# SCH_SA45_DaughterCard.net
KiCad netlist of a schematic drawn in Altium Designer
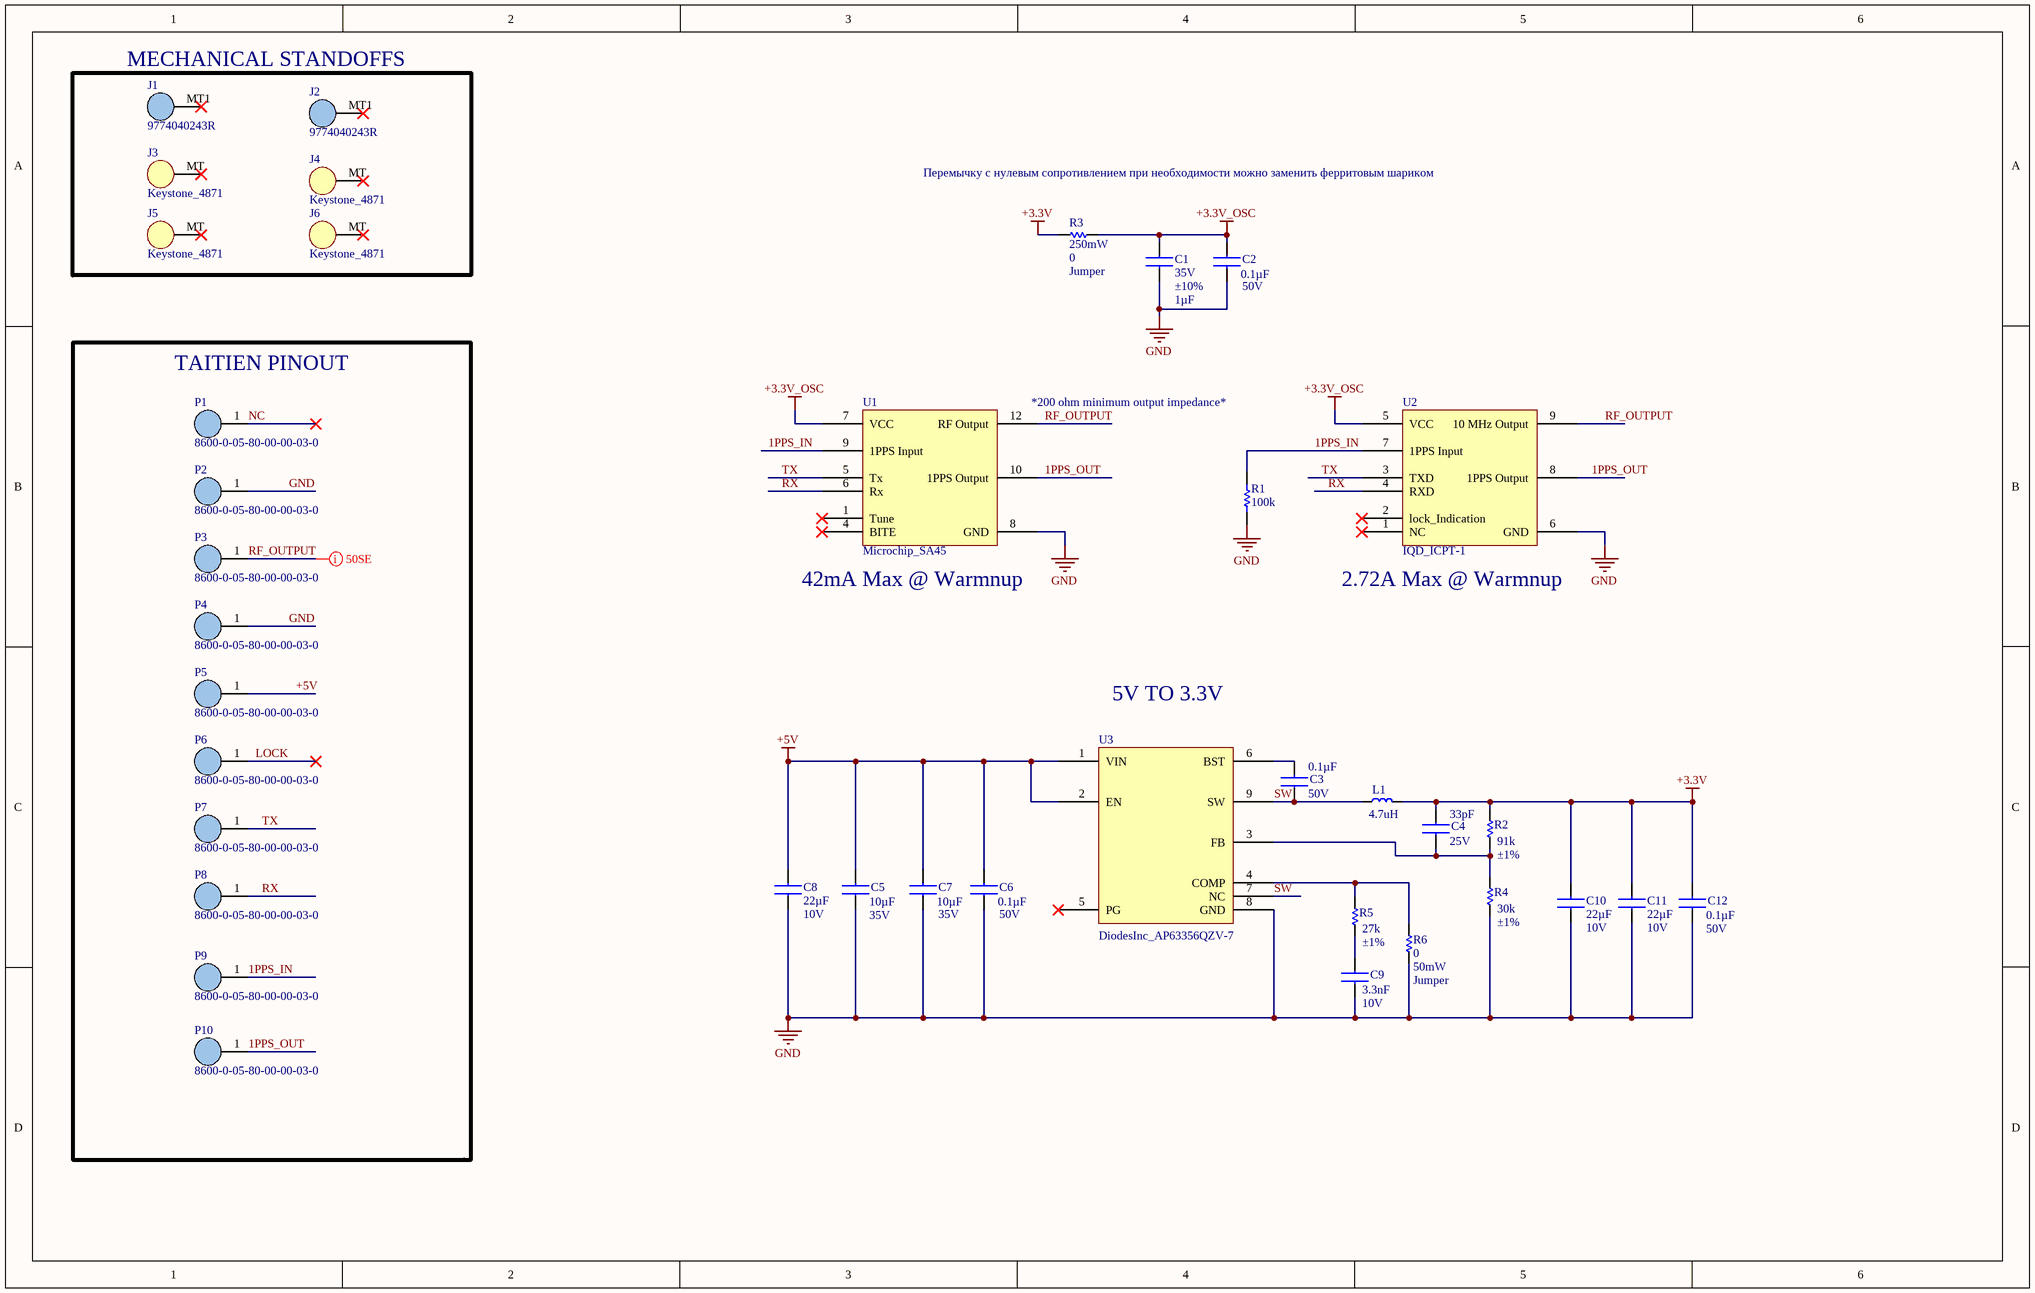
[diagram p0: SCH_SA45_DaughterCard.SchDoc]

(export (version "E")
  (design (tool "Eeschema 10.0.6"))
  (components
    (comp (ref "C1")
      (value "Murata_GRM155R6YA105KE11D")
      (footprint "CAPC1005X061N")
      (description "CAP, CER, X5R, 1UF, 10%, 35V, 0402, 0.55MM T")
      (fields
        (field (name "VOLTAGE RATING") "35V")
        (field (name "TOLERANCE") "±10%")
        (field (name "CAPACITANCE") "1µF")
        (field (name "MANUFACTURER PART NUMBER") "GRM155R6YA105KE11D")
        (field (name "MANUFACTURER") "Murata")
      )
      (libsource (lib "RL Research Altium Server") (part "Capacitor_300mil"))
    )
    (comp (ref "C2")
      (value "Murata_GRM155R61H104KE14D")
      (footprint "CAPC1005X055N")
      (description "CAP, CER, X5R, 0.10UF, 10%, 50V, 0402, 0.55MM T")
      (fields
        (field (name "TOLERANCE") "±10%")
        (field (name "VOLTAGE RATING") "50V")
        (field (name "MANUFACTURER PART NUMBER") "GRM155R61H104KE14D")
        (field (name "CAPACITANCE") "0.1µF")
      )
      (libsource (lib "RL Research Altium Server") (part "Capacitor_300mil"))
    )
    (comp (ref "C3")
      (value "Murata_GRM155R61H104KE14D")
      (footprint "CAPC1005X055N")
      (description "CAP, CER, X5R, 0.10UF, 10%, 50V, 0402, 0.55MM T")
      (fields
        (field (name "TOLERANCE") "±10%")
        (field (name "VOLTAGE RATING") "50V")
        (field (name "MANUFACTURER PART NUMBER") "GRM155R61H104KE14D")
        (field (name "CAPACITANCE") "0.1µF")
      )
      (libsource (lib "RL Research Altium Server") (part "Capacitor_300mil"))
    )
    (comp (ref "C4")
      (value "Murata_GRM0335C1E330JA01D")
      (footprint "CAPC0603X033N")
      (description "CAP, CER, NP0, 33PF, 5%, 25V, 0201, 0.33MM T")
      (fields
        (field (name "MANUFACTURER") "Murata")
        (field (name "CAPACITANCE") "33pF")
        (field (name "TOLERANCE") "±5%")
        (field (name "VOLTAGE RATING") "25V")
      )
      (libsource (lib "RL Research Altium Server") (part "Capacitor_300mil"))
    )
    (comp (ref "C5")
      (value "Murata_GRM21BR6YA106KE43L")
      (footprint "CAPC2013X145N")
      (description "CAP, CER, X5R, 10UF, 10%, 35V, 0805, 1.45MM T")
      (fields
        (field (name "MANUFACTURER") "Murata")
        (field (name "MANUFACTURER PART NUMBER") "GRM21BR6YA106KE43L")
        (field (name "VOLTAGE RATING") "35V")
        (field (name "CAPACITANCE") "10µF")
      )
      (libsource (lib "RL Research Altium Server") (part "Capacitor_300mil"))
    )
    (comp (ref "C6")
      (value "Murata_GRM155R61H104KE14D")
      (footprint "CAPC1005X055N")
      (description "CAP, CER, X5R, 0.10UF, 10%, 50V, 0402, 0.55MM T")
      (fields
        (field (name "TOLERANCE") "±10%")
        (field (name "VOLTAGE RATING") "50V")
        (field (name "MANUFACTURER PART NUMBER") "GRM155R61H104KE14D")
        (field (name "CAPACITANCE") "0.1µF")
      )
      (libsource (lib "RL Research Altium Server") (part "Capacitor_300mil"))
    )
    (comp (ref "C7")
      (value "Murata_GRM21BR6YA106KE43L")
      (footprint "CAPC2013X145N")
      (description "CAP, CER, X5R, 10UF, 10%, 35V, 0805, 1.45MM T")
      (fields
        (field (name "MANUFACTURER") "Murata")
        (field (name "MANUFACTURER PART NUMBER") "GRM21BR6YA106KE43L")
        (field (name "VOLTAGE RATING") "35V")
        (field (name "CAPACITANCE") "10µF")
      )
      (libsource (lib "RL Research Altium Server") (part "Capacitor_300mil"))
    )
    (comp (ref "C8")
      (value "Murata_GRM21BR61A226ME51L")
      (footprint "CAPC2013X140N")
      (description "CAP, CER, X5R, 22UF, 20%, 10V, 0805, 1.40MM T")
      (fields
        (field (name "CAPACITANCE") "22µF")
        (field (name "VOLTAGE RATING") "10V")
        (field (name "MANUFACTURER PART NUMBER") "GRM21BR61A226ME51L")
        (field (name "TOLERANCE") "±20%")
      )
      (libsource (lib "FRL Altium Server") (part "Capacitor_300mil"))
    )
    (comp (ref "C9")
      (value "Murata_GRM033R61A332KA01D")
      (footprint "CAPC0603X033N")
      (description "CAP, CER, X5R, 3300PF, 10%, 10V, 0201, 0.33MM T")
      (fields
        (field (name "TOLERANCE") "±10%")
        (field (name "MANUFACTURER PART NUMBER") "GRM033R61A332KA01D")
        (field (name "CAPACITANCE") "3.3nF")
        (field (name "VOLTAGE RATING") "10V")
      )
      (libsource (lib "RL Research Altium Server") (part "Capacitor_300mil"))
    )
    (comp (ref "C10")
      (value "Murata_GRM21BR61A226ME51L")
      (footprint "CAPC2013X140N")
      (description "CAP, CER, X5R, 22UF, 20%, 10V, 0805, 1.40MM T")
      (fields
        (field (name "CAPACITANCE") "22µF")
        (field (name "VOLTAGE RATING") "10V")
        (field (name "MANUFACTURER PART NUMBER") "GRM21BR61A226ME51L")
        (field (name "TOLERANCE") "±20%")
      )
      (libsource (lib "FRL Altium Server") (part "Capacitor_300mil"))
    )
    (comp (ref "C11")
      (value "Murata_GRM21BR61A226ME51L")
      (footprint "CAPC2013X140N")
      (description "CAP, CER, X5R, 22UF, 20%, 10V, 0805, 1.40MM T")
      (fields
        (field (name "CAPACITANCE") "22µF")
        (field (name "VOLTAGE RATING") "10V")
        (field (name "MANUFACTURER PART NUMBER") "GRM21BR61A226ME51L")
        (field (name "TOLERANCE") "±20%")
      )
      (libsource (lib "FRL Altium Server") (part "Capacitor_300mil"))
    )
    (comp (ref "C12")
      (value "Murata_GRM155R61H104KE14D")
      (footprint "CAPC1005X055N")
      (description "CAP, CER, X5R, 0.10UF, 10%, 50V, 0402, 0.55MM T")
      (fields
        (field (name "TOLERANCE") "±10%")
        (field (name "VOLTAGE RATING") "50V")
        (field (name "MANUFACTURER PART NUMBER") "GRM155R61H104KE14D")
        (field (name "CAPACITANCE") "0.1µF")
      )
      (libsource (lib "RL Research Altium Server") (part "Capacitor_300mil"))
    )
    (comp (ref "J1")
      (value "Wurth_9774040243R")
      (footprint "TH000V_300DIAx400_001mt_9774040243R")
      (description "STANDOFF, ROUND, M2X0.4 STEEL 4MM, 9774040243R")
      (fields
        (field (name "MANUFACTURER PART NUMBER") "9774040243R")
        (field (name "MANUFACTURER") "Wurth Elektronik")
      )
      (libsource (lib "FRL Altium Server") (part "CONN_SR_000pin_001mt_RND_F"))
    )
    (comp (ref "J2")
      (value "Wurth_9774040243R")
      (footprint "TH000V_300DIAx400_001mt_9774040243R")
      (description "STANDOFF, ROUND, M2X0.4 STEEL 4MM, 9774040243R")
      (fields
        (field (name "MANUFACTURER PART NUMBER") "9774040243R")
        (field (name "MANUFACTURER") "Wurth Elektronik")
      )
      (libsource (lib "FRL Altium Server") (part "CONN_SR_000pin_001mt_RND_F"))
    )
    (comp (ref "J3")
      (value "Keystone_4871")
      (footprint "Keystone_4871")
      (fields
        (field (name "MANUFACTURER") "Keystone Electronics")
        (field (name "MANUFACTURER PART NUMBER") "4871")
      )
      (libsource (lib "SCH_SA45_DaughterCard") (part "Keystone_4871"))
    )
    (comp (ref "J4")
      (value "Keystone_4871")
      (footprint "Keystone_4871")
      (fields
        (field (name "MANUFACTURER") "Keystone Electronics")
        (field (name "MANUFACTURER PART NUMBER") "4871")
      )
      (libsource (lib "SCH_SA45_DaughterCard") (part "Keystone_4871"))
    )
    (comp (ref "J5")
      (value "Keystone_4871")
      (footprint "Keystone_4871")
      (fields
        (field (name "MANUFACTURER") "Keystone Electronics")
        (field (name "MANUFACTURER PART NUMBER") "4871")
      )
      (libsource (lib "SCH_SA45_DaughterCard") (part "Keystone_4871"))
    )
    (comp (ref "J6")
      (value "Keystone_4871")
      (footprint "Keystone_4871")
      (fields
        (field (name "MANUFACTURER") "Keystone Electronics")
        (field (name "MANUFACTURER PART NUMBER") "4871")
      )
      (libsource (lib "SCH_SA45_DaughterCard") (part "Keystone_4871"))
    )
    (comp (ref "L1")
      (value "4.7uH")
      (footprint "Eaton_HCM0703-4R7-R")
      (fields (field (name "MANUFACTURER") "Eaton") (field (name "MANUFACTURER PART NUMBER") "HCM0703-4R7-R"))
      (libsource (lib "SCH_SA45_DaughterCard") (part "Inductor_Eaton"))
    )
    (comp (ref "P1")
      (value "Mill-Max_8600-0-05-80-00-00-03-0")
      (footprint "TH001V_109DIA_000mt_8600-0")
      (description "CONN, PC PIN, PRESS-FIT, 10.16MM LENGTH, TIN, TH")
      (fields
        (field (name "MANUFACTURER PART NUMBER") "8600-0-05-80-00-00-03-0")
        (field (name "MANUFACTURER") "Mill-Max Manufacturing Corp.")
      )
      (libsource (lib "FRL Altium Server") (part "CONN_SR_001pin_000mt_RND_M"))
    )
    (comp (ref "P2")
      (value "Mill-Max_8600-0-05-80-00-00-03-0")
      (footprint "TH001V_109DIA_000mt_8600-0")
      (description "CONN, PC PIN, PRESS-FIT, 10.16MM LENGTH, TIN, TH")
      (fields
        (field (name "MANUFACTURER PART NUMBER") "8600-0-05-80-00-00-03-0")
        (field (name "MANUFACTURER") "Mill-Max Manufacturing Corp.")
      )
      (libsource (lib "FRL Altium Server") (part "CONN_SR_001pin_000mt_RND_M"))
    )
    (comp (ref "P3")
      (value "Mill-Max_8600-0-05-80-00-00-03-0")
      (footprint "TH001V_109DIA_000mt_8600-0")
      (description "CONN, PC PIN, PRESS-FIT, 10.16MM LENGTH, TIN, TH")
      (fields
        (field (name "MANUFACTURER PART NUMBER") "8600-0-05-80-00-00-03-0")
        (field (name "MANUFACTURER") "Mill-Max Manufacturing Corp.")
      )
      (libsource (lib "FRL Altium Server") (part "CONN_SR_001pin_000mt_RND_M"))
    )
    (comp (ref "P4")
      (value "Mill-Max_8600-0-05-80-00-00-03-0")
      (footprint "TH001V_109DIA_000mt_8600-0")
      (description "CONN, PC PIN, PRESS-FIT, 10.16MM LENGTH, TIN, TH")
      (fields
        (field (name "MANUFACTURER PART NUMBER") "8600-0-05-80-00-00-03-0")
        (field (name "MANUFACTURER") "Mill-Max Manufacturing Corp.")
      )
      (libsource (lib "FRL Altium Server") (part "CONN_SR_001pin_000mt_RND_M"))
    )
    (comp (ref "P5")
      (value "Mill-Max_8600-0-05-80-00-00-03-0")
      (footprint "TH001V_109DIA_000mt_8600-0")
      (description "CONN, PC PIN, PRESS-FIT, 10.16MM LENGTH, TIN, TH")
      (fields
        (field (name "MANUFACTURER PART NUMBER") "8600-0-05-80-00-00-03-0")
        (field (name "MANUFACTURER") "Mill-Max Manufacturing Corp.")
      )
      (libsource (lib "FRL Altium Server") (part "CONN_SR_001pin_000mt_RND_M"))
    )
    (comp (ref "P6")
      (value "Mill-Max_8600-0-05-80-00-00-03-0")
      (footprint "TH001V_109DIA_000mt_8600-0")
      (description "CONN, PC PIN, PRESS-FIT, 10.16MM LENGTH, TIN, TH")
      (fields
        (field (name "MANUFACTURER PART NUMBER") "8600-0-05-80-00-00-03-0")
        (field (name "MANUFACTURER") "Mill-Max Manufacturing Corp.")
      )
      (libsource (lib "FRL Altium Server") (part "CONN_SR_001pin_000mt_RND_M"))
    )
    (comp (ref "P7")
      (value "Mill-Max_8600-0-05-80-00-00-03-0")
      (footprint "TH001V_109DIA_000mt_8600-0")
      (description "CONN, PC PIN, PRESS-FIT, 10.16MM LENGTH, TIN, TH")
      (fields
        (field (name "MANUFACTURER PART NUMBER") "8600-0-05-80-00-00-03-0")
        (field (name "MANUFACTURER") "Mill-Max Manufacturing Corp.")
      )
      (libsource (lib "FRL Altium Server") (part "CONN_SR_001pin_000mt_RND_M"))
    )
    (comp (ref "P8")
      (value "Mill-Max_8600-0-05-80-00-00-03-0")
      (footprint "TH001V_109DIA_000mt_8600-0")
      (description "CONN, PC PIN, PRESS-FIT, 10.16MM LENGTH, TIN, TH")
      (fields
        (field (name "MANUFACTURER PART NUMBER") "8600-0-05-80-00-00-03-0")
        (field (name "MANUFACTURER") "Mill-Max Manufacturing Corp.")
      )
      (libsource (lib "FRL Altium Server") (part "CONN_SR_001pin_000mt_RND_M"))
    )
    (comp (ref "P9")
      (value "Mill-Max_8600-0-05-80-00-00-03-0")
      (footprint "TH001V_109DIA_000mt_8600-0")
      (description "CONN, PC PIN, PRESS-FIT, 10.16MM LENGTH, TIN, TH")
      (fields
        (field (name "MANUFACTURER PART NUMBER") "8600-0-05-80-00-00-03-0")
        (field (name "MANUFACTURER") "Mill-Max Manufacturing Corp.")
      )
      (libsource (lib "FRL Altium Server") (part "CONN_SR_001pin_000mt_RND_M"))
    )
    (comp (ref "P10")
      (value "Mill-Max_8600-0-05-80-00-00-03-0")
      (footprint "TH001V_109DIA_000mt_8600-0")
      (description "CONN, PC PIN, PRESS-FIT, 10.16MM LENGTH, TIN, TH")
      (fields
        (field (name "MANUFACTURER PART NUMBER") "8600-0-05-80-00-00-03-0")
        (field (name "MANUFACTURER") "Mill-Max Manufacturing Corp.")
      )
      (libsource (lib "FRL Altium Server") (part "CONN_SR_001pin_000mt_RND_M"))
    )
    (comp (ref "R1")
      (value "100k")
      (footprint "RESC1608X55X30ML15T15")
      (fields
        (field (name "MANUFACTURER") "Panasonic")
        (field (name "MANUFACTURER PART NUMBER") "ERJ-3EKF1003V")
      )
      (libsource (lib "Altium Content Vault") (part "RES"))
    )
    (comp (ref "R2")
      (value "Yageo_RC0402FR-0791KL")
      (footprint "RESC1005X040N")
      (description "RES SMD 91K OHM 1% 1/16W 0402")
      (fields
        (field (name "TOLERANCE") "±1%")
        (field (name "MANUFACTURER PART NUMBER") "RC0402FR-0791KL")
        (field (name "MANUFACTURER") "Yageo")
        (field (name "RESISTANCE") "91k")
      )
      (libsource (lib "RL Research Altium Server") (part "Resistor_300mil"))
    )
    (comp (ref "R3")
      (value "Yageo_RC1206JR-070RL")
      (footprint "RESC3216X070N")
      (description "RES, 0 OHM, 2A, 1/4W, 1206")
      (fields
        (field (name "POWER (WATTS)") "250mW")
        (field (name "RESISTANCE") "0")
        (field (name "MANUFACTURER PART NUMBER") "RC1206JR-070RL")
        (field (name "MANUFACTURER") "Yageo")
        (field (name "TOLERANCE") "Jumper")
      )
      (libsource (lib "RL Research Altium Server") (part "Resistor_300mil"))
    )
    (comp (ref "R4")
      (value "Yageo_RC0402FR-0730KL")
      (footprint "RESC1005X040N")
      (description "RES SMD 30K OHM 1% 1/16W 0402")
      (fields
        (field (name "MANUFACTURER PART NUMBER") "RC0402FR-0730KL")
        (field (name "TOLERANCE") "±1%")
        (field (name "RESISTANCE") "30k")
        (field (name "MANUFACTURER") "Yageo")
      )
      (libsource (lib "RL Research Altium Server") (part "Resistor_300mil"))
    )
    (comp (ref "R5")
      (value "Panasonic_ERJ-2RKF2702X")
      (footprint "RESC1005X040N")
      (description "RES, 27K OHM, 1%, 1/10W, 100PPM/C, 0402")
      (fields
        (field (name "TOLERANCE") "±1%")
        (field (name "RESISTANCE") "27k")
        (field (name "MANUFACTURER") "Panasonic")
        (field (name "MANUFACTURER PART NUMBER") "ERJ-2RKF2702X")
      )
      (libsource (lib "RL Research Altium Server") (part "Resistor_300mil"))
    )
    (comp (ref "R6")
      (value "Yageo_RC0201JR-070RL")
      (footprint "RESC0603X026N")
      (description "RES, 0.0 OHM, 0.5A, 1/20W, 0201")
      (fields
        (field (name "RESISTANCE") "0")
        (field (name "MANUFACTURER PART NUMBER") "RC0201JR-070RL")
        (field (name "MANUFACTURER") "Yageo")
        (field (name "POWER (WATTS)") "50mW")
        (field (name "TOLERANCE") "Jumper")
      )
      (libsource (lib "RL Research Altium Server") (part "Resistor_300mil"))
    )
    (comp (ref "U1")
      (value "Microchip_SA45")
      (footprint "Microchip_SA45")
      (fields
        (field (name "MANUFACTURER") "Microchip")
        (field (name "MANUFACTURER PART NUMBER") "090-02984-001")
      )
      (libsource (lib "SCH_SA45_DaughterCard") (part "Microchip_SA45"))
    )
    (comp (ref "U2")
      (value "IQD_ICPT-1")
      (footprint "IQD_ICPT-1")
      (fields (field (name "MANUFACTURER") "IQD") (field (name "MANUFACTURER PART NUMBER") "IQD-ICPT-1"))
      (libsource (lib "SCH_SA45_DaughterCard") (part "IQD_ICPT-1"))
    )
    (comp (ref "U3")
      (value "DiodesInc_AP63356QZV-7")
      (footprint "DiodesInc_AP63356QZV-7")
      (fields
        (field (name "MANUFACTURER") "Diodes Incorporated")
        (field (name "MANUFACTURER PART NUMBER") "AP63356QZV-7")
      )
      (libsource (lib "SCH_SA45_DaughterCard") (part "DiodesInc_AP63356QZV-7"))
    )
  )
  (nets
    (net (code "1") (name "+3.3V") (class "Default")
      (node (ref "C10") (pin "1") (pinfunction "1_1") (pintype "passive"))
      (node (ref "C11") (pin "1") (pinfunction "1_1") (pintype "passive"))
      (node (ref "C12") (pin "1") (pinfunction "1_1") (pintype "passive"))
      (node (ref "C4") (pin "1") (pinfunction "1_1") (pintype "passive"))
      (node (ref "L1") (pin "2") (pinfunction "2_2") (pintype "passive"))
      (node (ref "R2") (pin "1") (pinfunction "1_1") (pintype "passive"))
      (node (ref "R3") (pin "1") (pinfunction "1_1") (pintype "passive"))
    )
    (net (code "2") (name "+3.3V_OSC") (class "Default")
      (node (ref "C1") (pin "1") (pinfunction "1_1") (pintype "passive"))
      (node (ref "C2") (pin "1") (pinfunction "1_1") (pintype "passive"))
      (node (ref "R3") (pin "2") (pinfunction "2_2") (pintype "passive"))
      (node (ref "U1") (pin "7") (pinfunction "VCC_7") (pintype "passive"))
      (node (ref "U2") (pin "5") (pinfunction "VCC_5") (pintype "passive"))
    )
    (net (code "3") (name "+5V") (class "Default")
      (node (ref "C5") (pin "1") (pinfunction "1_1") (pintype "passive"))
      (node (ref "C6") (pin "1") (pinfunction "1_1") (pintype "passive"))
      (node (ref "C7") (pin "1") (pinfunction "1_1") (pintype "passive"))
      (node (ref "C8") (pin "1") (pinfunction "1_1") (pintype "passive"))
      (node (ref "P5") (pin "1") (pinfunction "1_1") (pintype "passive"))
      (node (ref "U3") (pin "1") (pinfunction "VIN_1") (pintype "passive"))
      (node (ref "U3") (pin "2") (pinfunction "EN_2") (pintype "passive"))
    )
    (net (code "4") (name "/1PPS_IN") (class "Default")
      (node (ref "P9") (pin "1") (pinfunction "1_1") (pintype "passive"))
      (node (ref "R1") (pin "2") (pinfunction "2_2") (pintype "passive"))
      (node (ref "U1") (pin "9") (pinfunction "1PPS_Input_9") (pintype "passive"))
      (node (ref "U2") (pin "7") (pinfunction "1PPS_Input_7") (pintype "passive"))
    )
    (net (code "5") (name "/1PPS_OUT") (class "Default")
      (node (ref "P10") (pin "1") (pinfunction "1_1") (pintype "passive"))
      (node (ref "U1") (pin "10") (pinfunction "1PPS_Output_10") (pintype "passive"))
      (node (ref "U2") (pin "8") (pinfunction "1PPS_Output_8") (pintype "passive"))
    )
    (net (code "6") (name "/LOCK") (class "Default")
      (node (ref "P6") (pin "1") (pinfunction "1_1") (pintype "passive+no_connect"))
    )
    (net (code "7") (name "/NC") (class "Default")
      (node (ref "P1") (pin "1") (pinfunction "1_1") (pintype "passive+no_connect"))
    )
    (net (code "8") (name "/RF_OUTPUT") (class "Default")
      (node (ref "P3") (pin "1") (pinfunction "1_1") (pintype "passive"))
      (node (ref "U1") (pin "12") (pinfunction "RF_Output_12") (pintype "passive"))
      (node (ref "U2") (pin "9") (pinfunction "10_MHz_Output_9") (pintype "passive"))
    )
    (net (code "9") (name "/RX") (class "Default")
      (node (ref "P8") (pin "1") (pinfunction "1_1") (pintype "passive"))
      (node (ref "U1") (pin "6") (pinfunction "Rx_6") (pintype "passive"))
      (node (ref "U2") (pin "4") (pinfunction "RXD_4") (pintype "passive"))
    )
    (net (code "10") (name "/SW") (class "Default")
      (node (ref "C3") (pin "2") (pinfunction "2_2") (pintype "passive"))
      (node (ref "L1") (pin "1") (pinfunction "1_1") (pintype "passive"))
      (node (ref "U3") (pin "7") (pinfunction "NC_7") (pintype "passive"))
      (node (ref "U3") (pin "9") (pinfunction "SW_9") (pintype "passive"))
    )
    (net (code "11") (name "/TX") (class "Default")
      (node (ref "P7") (pin "1") (pinfunction "1_1") (pintype "passive"))
      (node (ref "U1") (pin "5") (pinfunction "Tx_5") (pintype "passive"))
      (node (ref "U2") (pin "3") (pinfunction "TXD_3") (pintype "passive"))
    )
    (net (code "12") (name "GND") (class "Default")
      (node (ref "C1") (pin "2") (pinfunction "2_2") (pintype "passive"))
      (node (ref "C10") (pin "2") (pinfunction "2_2") (pintype "passive"))
      (node (ref "C11") (pin "2") (pinfunction "2_2") (pintype "passive"))
      (node (ref "C12") (pin "2") (pinfunction "2_2") (pintype "passive"))
      (node (ref "C2") (pin "2") (pinfunction "2_2") (pintype "passive"))
      (node (ref "C5") (pin "2") (pinfunction "2_2") (pintype "passive"))
      (node (ref "C6") (pin "2") (pinfunction "2_2") (pintype "passive"))
      (node (ref "C7") (pin "2") (pinfunction "2_2") (pintype "passive"))
      (node (ref "C8") (pin "2") (pinfunction "2_2") (pintype "passive"))
      (node (ref "C9") (pin "2") (pinfunction "2_2") (pintype "passive"))
      (node (ref "P2") (pin "1") (pinfunction "1_1") (pintype "passive"))
      (node (ref "P4") (pin "1") (pinfunction "1_1") (pintype "passive"))
      (node (ref "R1") (pin "1") (pinfunction "1_1") (pintype "passive"))
      (node (ref "R4") (pin "2") (pinfunction "2_2") (pintype "passive"))
      (node (ref "R6") (pin "2") (pinfunction "2_2") (pintype "passive"))
      (node (ref "U1") (pin "8") (pinfunction "GND_8") (pintype "passive"))
      (node (ref "U2") (pin "6") (pinfunction "GND_6") (pintype "passive"))
      (node (ref "U3") (pin "8") (pinfunction "GND_8") (pintype "passive"))
    )
    (net (code "13") (name "Net-(C9-Pad1)") (class "Default")
      (node (ref "C9") (pin "1") (pinfunction "1_1") (pintype "passive"))
      (node (ref "R5") (pin "2") (pinfunction "2_2") (pintype "passive"))
    )
    (net (code "14") (name "Net-(U3-BST)") (class "Default")
      (node (ref "C3") (pin "1") (pinfunction "1_1") (pintype "passive"))
      (node (ref "U3") (pin "6") (pinfunction "BST_6") (pintype "passive"))
    )
    (net (code "15") (name "Net-(U3-COMP)") (class "Default")
      (node (ref "R5") (pin "1") (pinfunction "1_1") (pintype "passive"))
      (node (ref "R6") (pin "1") (pinfunction "1_1") (pintype "passive"))
      (node (ref "U3") (pin "4") (pinfunction "COMP_4") (pintype "passive"))
    )
    (net (code "16") (name "Net-(U3-FB)") (class "Default")
      (node (ref "C4") (pin "2") (pinfunction "2_2") (pintype "passive"))
      (node (ref "R2") (pin "2") (pinfunction "2_2") (pintype "passive"))
      (node (ref "R4") (pin "1") (pinfunction "1_1") (pintype "passive"))
      (node (ref "U3") (pin "3") (pinfunction "FB_3") (pintype "passive"))
    )
    (net (code "17") (name "unconnected-(J1-PadMT1)") (class "Default")
      (node (ref "J1") (pin "MT1") (pinfunction "MT1_MT1") (pintype "passive+no_connect"))
    )
    (net (code "18") (name "unconnected-(J2-PadMT1)") (class "Default")
      (node (ref "J2") (pin "MT1") (pinfunction "MT1_MT1") (pintype "passive+no_connect"))
    )
    (net (code "19") (name "unconnected-(J3-PadMT)") (class "Default")
      (node (ref "J3") (pin "MT") (pinfunction "MT_MT") (pintype "passive+no_connect"))
    )
    (net (code "20") (name "unconnected-(J4-PadMT)") (class "Default")
      (node (ref "J4") (pin "MT") (pinfunction "MT_MT") (pintype "passive+no_connect"))
    )
    (net (code "21") (name "unconnected-(J5-PadMT)") (class "Default")
      (node (ref "J5") (pin "MT") (pinfunction "MT_MT") (pintype "passive+no_connect"))
    )
    (net (code "22") (name "unconnected-(J6-PadMT)") (class "Default")
      (node (ref "J6") (pin "MT") (pinfunction "MT_MT") (pintype "passive+no_connect"))
    )
    (net (code "23") (name "unconnected-(U1-BITE-Pad4)") (class "Default")
      (node (ref "U1") (pin "4") (pinfunction "BITE_4") (pintype "passive+no_connect"))
    )
    (net (code "24") (name "unconnected-(U1-Tune-Pad1)") (class "Default")
      (node (ref "U1") (pin "1") (pinfunction "Tune_1") (pintype "passive+no_connect"))
    )
    (net (code "25") (name "unconnected-(U2-NC-Pad1)") (class "Default")
      (node (ref "U2") (pin "1") (pinfunction "NC_1") (pintype "passive+no_connect"))
    )
    (net (code "26") (name "unconnected-(U2-lock_Indication-Pad2)") (class "Default")
      (node (ref "U2") (pin "2") (pinfunction "lock_Indication_2") (pintype "passive+no_connect"))
    )
    (net (code "27") (name "unconnected-(U3-PG-Pad5)") (class "Default")
      (node (ref "U3") (pin "5") (pinfunction "PG_5") (pintype "passive+no_connect"))
    )
  )
)
